# Fri3d_2024_Exp0_Keyboard_01.net
KiCad netlist of a schematic drawn in Altium Designer
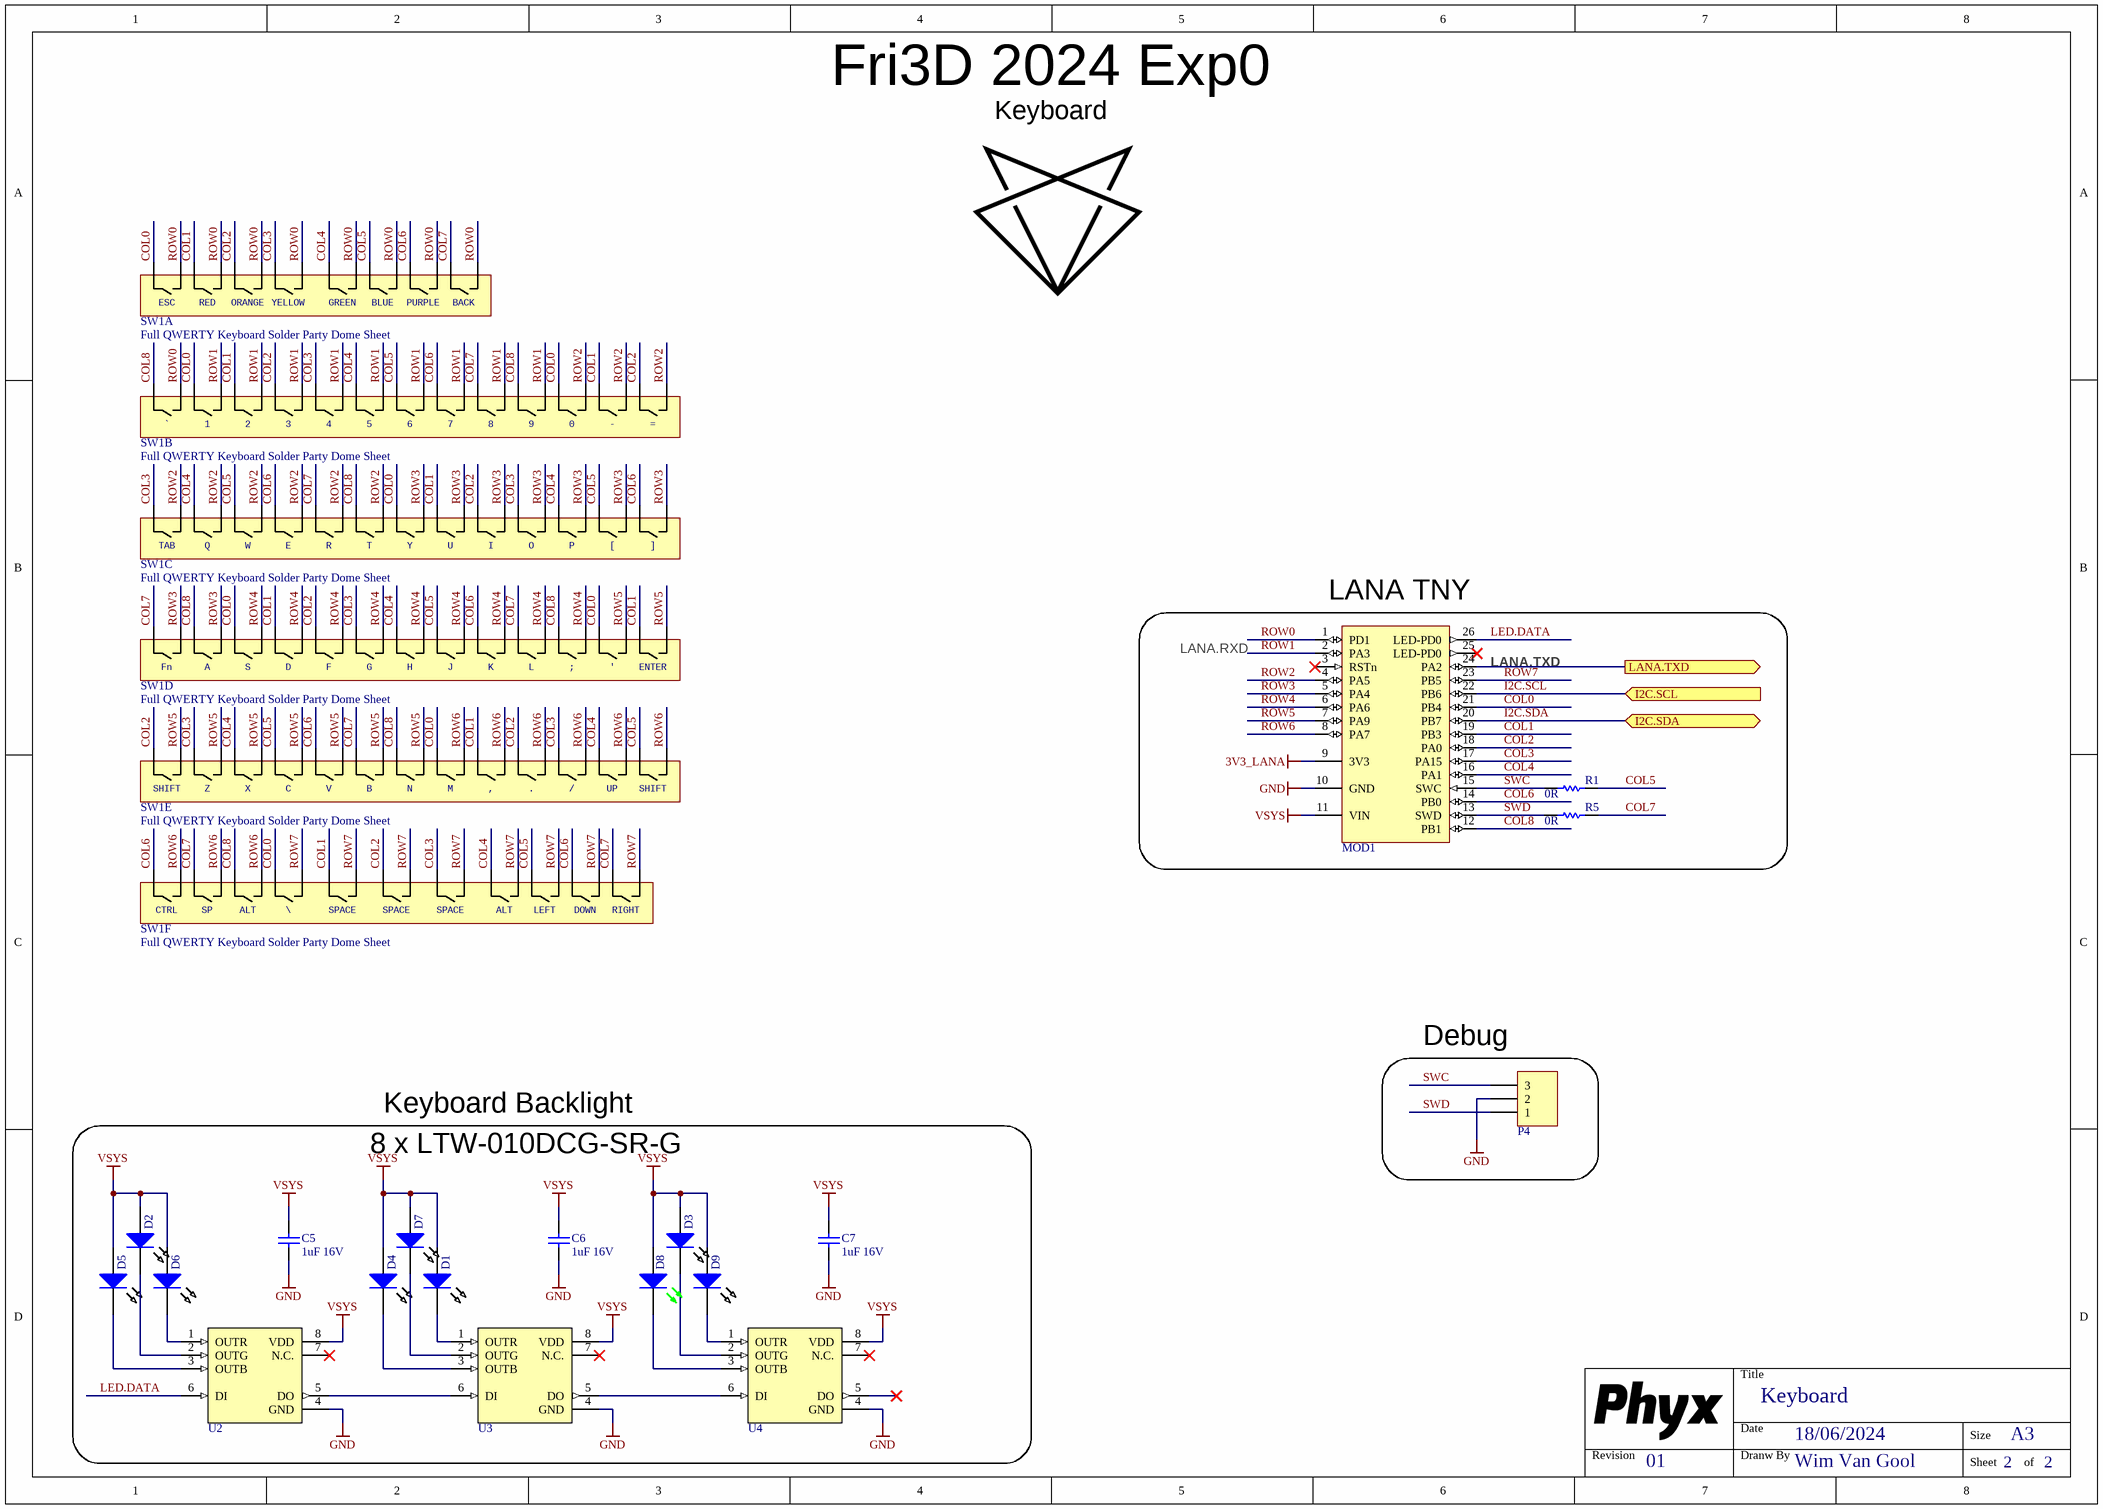
[diagram p0: Fri3d_2024_Exp0_Keyboard_01.SchDoc]

(export (version "E")
  (design (tool "Eeschema 10.0.6"))
  (components
    (comp (ref "C5")
      (value "1uF 16V")
      (footprint "C0603_N")
      (description "Capacitor Ceramic")
      (fields (field (name "Comment") "CAP_CERAMIC"))
      (libsource (lib "Phyx_Components") (part "CAP_CERAMIC"))
    )
    (comp (ref "C6")
      (value "1uF 16V")
      (footprint "C0603_N")
      (description "Capacitor Ceramic")
      (fields (field (name "Comment") "CAP_CERAMIC"))
      (libsource (lib "Phyx_Components") (part "CAP_CERAMIC"))
    )
    (comp (ref "C7")
      (value "1uF 16V")
      (footprint "C0603_N")
      (description "Capacitor Ceramic")
      (fields (field (name "Comment") "CAP_CERAMIC"))
      (libsource (lib "Phyx_Components") (part "CAP_CERAMIC"))
    )
    (comp (ref "D1")
      (value "Side emitting Cool White LED 3.0V 30mA 120° 2900mcd")
      (footprint "LITE_LTW-010DCG")
      (description "=Description")
      (libsource (lib "Phyx_Components") (part "LED_WHITE"))
    )
    (comp (ref "D2")
      (value "Side emitting Cool White LED 3.0V 30mA 120° 2900mcd")
      (footprint "LITE_LTW-010DCG")
      (description "=Description")
      (libsource (lib "Phyx_Components") (part "LED_WHITE"))
    )
    (comp (ref "D3")
      (value "Side emitting Cool White LED 3.0V 30mA 120° 2900mcd")
      (footprint "LITE_LTW-010DCG")
      (description "=Description")
      (libsource (lib "Phyx_Components") (part "LED_WHITE"))
    )
    (comp (ref "D4")
      (value "Side emitting Cool White LED 3.0V 30mA 120° 2900mcd")
      (footprint "LITE_LTW-010DCG")
      (description "=Description")
      (libsource (lib "Phyx_Components") (part "LED_WHITE"))
    )
    (comp (ref "D5")
      (value "Side emitting Cool White LED 3.0V 30mA 120° 2900mcd")
      (footprint "LITE_LTW-010DCG")
      (description "=Description")
      (libsource (lib "Phyx_Components") (part "LED_WHITE"))
    )
    (comp (ref "D6")
      (value "Side emitting Cool White LED 3.0V 30mA 120° 2900mcd")
      (footprint "LITE_LTW-010DCG")
      (description "=Description")
      (libsource (lib "Phyx_Components") (part "LED_WHITE"))
    )
    (comp (ref "D7")
      (value "Side emitting Cool White LED 3.0V 30mA 120° 2900mcd")
      (footprint "LITE_LTW-010DCG")
      (description "=Description")
      (libsource (lib "Phyx_Components") (part "LED_WHITE"))
    )
    (comp (ref "D8")
      (value "Default 0805 Green LED")
      (footprint "LED_0805_GR")
      (description "=Description")
      (libsource (lib "Phyx_Components") (part "LED_GREEN"))
    )
    (comp (ref "D9")
      (value "Side emitting Cool White LED 3.0V 30mA 120° 2900mcd")
      (footprint "LITE_LTW-010DCG")
      (description "=Description")
      (libsource (lib "Phyx_Components") (part "LED_WHITE"))
    )
    (comp (ref "MOD1")
      (value "CH23V203 based TNY module")
      (footprint "PHYX_LANA_TNY_SMD")
      (libsource (lib "Phyx_Components") (part "PHYX_LANA_TNY_SMD"))
    )
    (comp (ref "P4")
      (value "Header 3")
      (footprint "HDR1X3")
      (libsource (lib "Phyx_Components") (part "Header 3"))
    )
    (comp (ref "R1")
      (value "0R")
      (footprint "R0603_N")
      (fields (field (name "Comment") "RESISTOR"))
      (libsource (lib "Phyx_Components") (part "RESISTOR"))
    )
    (comp (ref "R5")
      (value "0R")
      (footprint "R0603_N")
      (fields (field (name "Comment") "RESISTOR"))
      (libsource (lib "Phyx_Components") (part "RESISTOR"))
    )
    (comp (ref "SW1")
      (value "Full QWERTY Keyboard Solder Party Dome Sheet")
      (footprint "Solder_Party_Keyb")
      (libsource (lib "CONNECTORS") (part "Solder_Party_Keyb"))
    )
    (comp (ref "U2")
      (value "3 Channel CC LED Driver 20mA")
      (footprint "WS_FSOP-8")
      (description "WS2811F 3-Ch LED Driver")
      (libsource (lib "Phyx_Components") (part "WS_WS2811F"))
    )
    (comp (ref "U3")
      (value "3 Channel CC LED Driver 20mA")
      (footprint "WS_FSOP-8")
      (description "WS2811F 3-Ch LED Driver")
      (libsource (lib "Phyx_Components") (part "WS_WS2811F"))
    )
    (comp (ref "U4")
      (value "3 Channel CC LED Driver 20mA")
      (footprint "WS_FSOP-8")
      (description "WS2811F 3-Ch LED Driver")
      (libsource (lib "Phyx_Components") (part "WS_WS2811F"))
    )
  )
  (nets
    (net (code "2") (name "/COL0") (class "Default")
      (node (ref "MOD1") (pin "21") (pinfunction "PB4_21") (pintype "bidirectional"))
      (node (ref "SW1") (pin "1") (pinfunction "1_1") (pintype "passive"))
      (node (ref "SW1") (pin "109") (pinfunction "109_109") (pintype "passive"))
      (node (ref "SW1") (pin "127") (pinfunction "127_127") (pintype "passive"))
      (node (ref "SW1") (pin "19") (pinfunction "19_19") (pintype "passive"))
      (node (ref "SW1") (pin "37") (pinfunction "37_37") (pintype "passive"))
      (node (ref "SW1") (pin "55") (pinfunction "55_55") (pintype "passive"))
      (node (ref "SW1") (pin "73") (pinfunction "73_73") (pintype "passive"))
      (node (ref "SW1") (pin "91") (pinfunction "91_91") (pintype "passive"))
    )
    (net (code "3") (name "/COL1") (class "Default")
      (node (ref "MOD1") (pin "19") (pinfunction "PB3_19") (pintype "bidirectional"))
      (node (ref "SW1") (pin "111") (pinfunction "111_111") (pintype "passive"))
      (node (ref "SW1") (pin "129") (pinfunction "129_129") (pintype "passive"))
      (node (ref "SW1") (pin "21") (pinfunction "21_21") (pintype "passive"))
      (node (ref "SW1") (pin "3") (pinfunction "3_3") (pintype "passive"))
      (node (ref "SW1") (pin "39") (pinfunction "39_39") (pintype "passive"))
      (node (ref "SW1") (pin "57") (pinfunction "57_57") (pintype "passive"))
      (node (ref "SW1") (pin "75") (pinfunction "75_75") (pintype "passive"))
      (node (ref "SW1") (pin "93") (pinfunction "93_93") (pintype "passive"))
    )
    (net (code "4") (name "/COL2") (class "Default")
      (node (ref "MOD1") (pin "18") (pinfunction "PA0_18") (pintype "bidirectional"))
      (node (ref "SW1") (pin "113") (pinfunction "113_113") (pintype "passive"))
      (node (ref "SW1") (pin "131") (pinfunction "131_131") (pintype "passive"))
      (node (ref "SW1") (pin "23") (pinfunction "23_23") (pintype "passive"))
      (node (ref "SW1") (pin "41") (pinfunction "41_41") (pintype "passive"))
      (node (ref "SW1") (pin "5") (pinfunction "5_5") (pintype "passive"))
      (node (ref "SW1") (pin "59") (pinfunction "59_59") (pintype "passive"))
      (node (ref "SW1") (pin "77") (pinfunction "77_77") (pintype "passive"))
      (node (ref "SW1") (pin "95") (pinfunction "95_95") (pintype "passive"))
    )
    (net (code "5") (name "/COL3") (class "Default")
      (node (ref "MOD1") (pin "17") (pinfunction "PA15_17") (pintype "bidirectional"))
      (node (ref "SW1") (pin "115") (pinfunction "115_115") (pintype "passive"))
      (node (ref "SW1") (pin "133") (pinfunction "133_133") (pintype "passive"))
      (node (ref "SW1") (pin "25") (pinfunction "25_25") (pintype "passive"))
      (node (ref "SW1") (pin "43") (pinfunction "43_43") (pintype "passive"))
      (node (ref "SW1") (pin "61") (pinfunction "61_61") (pintype "passive"))
      (node (ref "SW1") (pin "7") (pinfunction "7_7") (pintype "passive"))
      (node (ref "SW1") (pin "79") (pinfunction "79_79") (pintype "passive"))
      (node (ref "SW1") (pin "97") (pinfunction "97_97") (pintype "passive"))
    )
    (net (code "6") (name "/COL4") (class "Default")
      (node (ref "MOD1") (pin "16") (pinfunction "PA1_16") (pintype "bidirectional"))
      (node (ref "SW1") (pin "117") (pinfunction "117_117") (pintype "passive"))
      (node (ref "SW1") (pin "135") (pinfunction "135_135") (pintype "passive"))
      (node (ref "SW1") (pin "27") (pinfunction "27_27") (pintype "passive"))
      (node (ref "SW1") (pin "45") (pinfunction "45_45") (pintype "passive"))
      (node (ref "SW1") (pin "63") (pinfunction "63_63") (pintype "passive"))
      (node (ref "SW1") (pin "81") (pinfunction "81_81") (pintype "passive"))
      (node (ref "SW1") (pin "9") (pinfunction "9_9") (pintype "passive"))
      (node (ref "SW1") (pin "99") (pinfunction "99_99") (pintype "passive"))
    )
    (net (code "7") (name "/COL5") (class "Default")
      (node (ref "R1") (pin "1") (pinfunction "1_1") (pintype "passive"))
      (node (ref "SW1") (pin "101") (pinfunction "101_101") (pintype "passive"))
      (node (ref "SW1") (pin "11") (pinfunction "11_11") (pintype "passive"))
      (node (ref "SW1") (pin "119") (pinfunction "119_119") (pintype "passive"))
      (node (ref "SW1") (pin "137") (pinfunction "137_137") (pintype "passive"))
      (node (ref "SW1") (pin "29") (pinfunction "29_29") (pintype "passive"))
      (node (ref "SW1") (pin "47") (pinfunction "47_47") (pintype "passive"))
      (node (ref "SW1") (pin "65") (pinfunction "65_65") (pintype "passive"))
      (node (ref "SW1") (pin "83") (pinfunction "83_83") (pintype "passive"))
    )
    (net (code "8") (name "/COL6") (class "Default")
      (node (ref "MOD1") (pin "14") (pinfunction "PB0_14") (pintype "bidirectional"))
      (node (ref "SW1") (pin "103") (pinfunction "103_103") (pintype "passive"))
      (node (ref "SW1") (pin "121") (pinfunction "121_121") (pintype "passive"))
      (node (ref "SW1") (pin "13") (pinfunction "13_13") (pintype "passive"))
      (node (ref "SW1") (pin "139") (pinfunction "139_139") (pintype "passive"))
      (node (ref "SW1") (pin "31") (pinfunction "31_31") (pintype "passive"))
      (node (ref "SW1") (pin "49") (pinfunction "49_49") (pintype "passive"))
      (node (ref "SW1") (pin "67") (pinfunction "67_67") (pintype "passive"))
      (node (ref "SW1") (pin "85") (pinfunction "85_85") (pintype "passive"))
    )
    (net (code "9") (name "/COL7") (class "Default")
      (node (ref "R5") (pin "1") (pinfunction "1_1") (pintype "passive"))
      (node (ref "SW1") (pin "105") (pinfunction "105_105") (pintype "passive"))
      (node (ref "SW1") (pin "123") (pinfunction "123_123") (pintype "passive"))
      (node (ref "SW1") (pin "141") (pinfunction "141_141") (pintype "passive"))
      (node (ref "SW1") (pin "15") (pinfunction "15_15") (pintype "passive"))
      (node (ref "SW1") (pin "33") (pinfunction "33_33") (pintype "passive"))
      (node (ref "SW1") (pin "51") (pinfunction "51_51") (pintype "passive"))
      (node (ref "SW1") (pin "69") (pinfunction "69_69") (pintype "passive"))
      (node (ref "SW1") (pin "87") (pinfunction "87_87") (pintype "passive"))
    )
    (net (code "10") (name "/COL8") (class "Default")
      (node (ref "MOD1") (pin "12") (pinfunction "PB1_12") (pintype "bidirectional"))
      (node (ref "SW1") (pin "107") (pinfunction "107_107") (pintype "passive"))
      (node (ref "SW1") (pin "125") (pinfunction "125_125") (pintype "passive"))
      (node (ref "SW1") (pin "17") (pinfunction "17_17") (pintype "passive"))
      (node (ref "SW1") (pin "35") (pinfunction "35_35") (pintype "passive"))
      (node (ref "SW1") (pin "53") (pinfunction "53_53") (pintype "passive"))
      (node (ref "SW1") (pin "71") (pinfunction "71_71") (pintype "passive"))
      (node (ref "SW1") (pin "89") (pinfunction "89_89") (pintype "passive"))
    )
    (net (code "11") (name "/I2C.SCL") (class "Default")
      (node (ref "MOD1") (pin "22") (pinfunction "PB6_22") (pintype "bidirectional"))
    )
    (net (code "12") (name "/I2C.SDA") (class "Default")
      (node (ref "MOD1") (pin "20") (pinfunction "PB7_20") (pintype "bidirectional"))
    )
    (net (code "13") (name "/LANA.TXD") (class "Default")
      (node (ref "MOD1") (pin "24") (pinfunction "PA2_24") (pintype "bidirectional"))
    )
    (net (code "14") (name "/LED.DATA") (class "Default")
      (node (ref "MOD1") (pin "26") (pinfunction "LED-PD0_26") (pintype "output"))
      (node (ref "U2") (pin "6") (pinfunction "DI_6") (pintype "input"))
    )
    (net (code "15") (name "/ROW0") (class "Default")
      (node (ref "MOD1") (pin "1") (pinfunction "PD1_1") (pintype "bidirectional"))
      (node (ref "SW1") (pin "10") (pinfunction "10_10") (pintype "passive"))
      (node (ref "SW1") (pin "12") (pinfunction "12_12") (pintype "passive"))
      (node (ref "SW1") (pin "14") (pinfunction "14_14") (pintype "passive"))
      (node (ref "SW1") (pin "16") (pinfunction "16_16") (pintype "passive"))
      (node (ref "SW1") (pin "18") (pinfunction "18_18") (pintype "passive"))
      (node (ref "SW1") (pin "2") (pinfunction "2_2") (pintype "passive"))
      (node (ref "SW1") (pin "4") (pinfunction "4_4") (pintype "passive"))
      (node (ref "SW1") (pin "6") (pinfunction "6_6") (pintype "passive"))
      (node (ref "SW1") (pin "8") (pinfunction "8_8") (pintype "passive"))
    )
    (net (code "16") (name "/ROW1") (class "Default")
      (node (ref "MOD1") (pin "2") (pinfunction "PA3_2") (pintype "bidirectional"))
      (node (ref "SW1") (pin "20") (pinfunction "20_20") (pintype "passive"))
      (node (ref "SW1") (pin "22") (pinfunction "22_22") (pintype "passive"))
      (node (ref "SW1") (pin "24") (pinfunction "24_24") (pintype "passive"))
      (node (ref "SW1") (pin "26") (pinfunction "26_26") (pintype "passive"))
      (node (ref "SW1") (pin "28") (pinfunction "28_28") (pintype "passive"))
      (node (ref "SW1") (pin "30") (pinfunction "30_30") (pintype "passive"))
      (node (ref "SW1") (pin "32") (pinfunction "32_32") (pintype "passive"))
      (node (ref "SW1") (pin "34") (pinfunction "34_34") (pintype "passive"))
      (node (ref "SW1") (pin "36") (pinfunction "36_36") (pintype "passive"))
    )
    (net (code "17") (name "/ROW2") (class "Default")
      (node (ref "MOD1") (pin "4") (pinfunction "PA5_4") (pintype "bidirectional"))
      (node (ref "SW1") (pin "38") (pinfunction "38_38") (pintype "passive"))
      (node (ref "SW1") (pin "40") (pinfunction "40_40") (pintype "passive"))
      (node (ref "SW1") (pin "42") (pinfunction "42_42") (pintype "passive"))
      (node (ref "SW1") (pin "44") (pinfunction "44_44") (pintype "passive"))
      (node (ref "SW1") (pin "46") (pinfunction "46_46") (pintype "passive"))
      (node (ref "SW1") (pin "48") (pinfunction "48_48") (pintype "passive"))
      (node (ref "SW1") (pin "50") (pinfunction "50_50") (pintype "passive"))
      (node (ref "SW1") (pin "52") (pinfunction "52_52") (pintype "passive"))
      (node (ref "SW1") (pin "54") (pinfunction "54_54") (pintype "passive"))
    )
    (net (code "18") (name "/ROW3") (class "Default")
      (node (ref "MOD1") (pin "5") (pinfunction "PA4_5") (pintype "bidirectional"))
      (node (ref "SW1") (pin "56") (pinfunction "56_56") (pintype "passive"))
      (node (ref "SW1") (pin "58") (pinfunction "58_58") (pintype "passive"))
      (node (ref "SW1") (pin "60") (pinfunction "60_60") (pintype "passive"))
      (node (ref "SW1") (pin "62") (pinfunction "62_62") (pintype "passive"))
      (node (ref "SW1") (pin "64") (pinfunction "64_64") (pintype "passive"))
      (node (ref "SW1") (pin "66") (pinfunction "66_66") (pintype "passive"))
      (node (ref "SW1") (pin "68") (pinfunction "68_68") (pintype "passive"))
      (node (ref "SW1") (pin "70") (pinfunction "70_70") (pintype "passive"))
      (node (ref "SW1") (pin "72") (pinfunction "72_72") (pintype "passive"))
    )
    (net (code "19") (name "/ROW4") (class "Default")
      (node (ref "MOD1") (pin "6") (pinfunction "PA6_6") (pintype "bidirectional"))
      (node (ref "SW1") (pin "74") (pinfunction "74_74") (pintype "passive"))
      (node (ref "SW1") (pin "76") (pinfunction "76_76") (pintype "passive"))
      (node (ref "SW1") (pin "78") (pinfunction "78_78") (pintype "passive"))
      (node (ref "SW1") (pin "80") (pinfunction "80_80") (pintype "passive"))
      (node (ref "SW1") (pin "82") (pinfunction "82_82") (pintype "passive"))
      (node (ref "SW1") (pin "84") (pinfunction "84_84") (pintype "passive"))
      (node (ref "SW1") (pin "86") (pinfunction "86_86") (pintype "passive"))
      (node (ref "SW1") (pin "88") (pinfunction "88_88") (pintype "passive"))
      (node (ref "SW1") (pin "90") (pinfunction "90_90") (pintype "passive"))
    )
    (net (code "20") (name "/ROW5") (class "Default")
      (node (ref "MOD1") (pin "7") (pinfunction "PA9_7") (pintype "bidirectional"))
      (node (ref "SW1") (pin "100") (pinfunction "100_100") (pintype "passive"))
      (node (ref "SW1") (pin "102") (pinfunction "102_102") (pintype "passive"))
      (node (ref "SW1") (pin "104") (pinfunction "104_104") (pintype "passive"))
      (node (ref "SW1") (pin "106") (pinfunction "106_106") (pintype "passive"))
      (node (ref "SW1") (pin "108") (pinfunction "108_108") (pintype "passive"))
      (node (ref "SW1") (pin "92") (pinfunction "92_92") (pintype "passive"))
      (node (ref "SW1") (pin "94") (pinfunction "94_94") (pintype "passive"))
      (node (ref "SW1") (pin "96") (pinfunction "96_96") (pintype "passive"))
      (node (ref "SW1") (pin "98") (pinfunction "98_98") (pintype "passive"))
    )
    (net (code "21") (name "/ROW6") (class "Default")
      (node (ref "MOD1") (pin "8") (pinfunction "PA7_8") (pintype "bidirectional"))
      (node (ref "SW1") (pin "110") (pinfunction "110_110") (pintype "passive"))
      (node (ref "SW1") (pin "112") (pinfunction "112_112") (pintype "passive"))
      (node (ref "SW1") (pin "114") (pinfunction "114_114") (pintype "passive"))
      (node (ref "SW1") (pin "116") (pinfunction "116_116") (pintype "passive"))
      (node (ref "SW1") (pin "118") (pinfunction "118_118") (pintype "passive"))
      (node (ref "SW1") (pin "120") (pinfunction "120_120") (pintype "passive"))
      (node (ref "SW1") (pin "122") (pinfunction "122_122") (pintype "passive"))
      (node (ref "SW1") (pin "124") (pinfunction "124_124") (pintype "passive"))
      (node (ref "SW1") (pin "126") (pinfunction "126_126") (pintype "passive"))
    )
    (net (code "22") (name "/ROW7") (class "Default")
      (node (ref "MOD1") (pin "23") (pinfunction "PB5_23") (pintype "bidirectional"))
      (node (ref "SW1") (pin "128") (pinfunction "128_128") (pintype "passive"))
      (node (ref "SW1") (pin "130") (pinfunction "130_130") (pintype "passive"))
      (node (ref "SW1") (pin "132") (pinfunction "132_132") (pintype "passive"))
      (node (ref "SW1") (pin "134") (pinfunction "134_134") (pintype "passive"))
      (node (ref "SW1") (pin "136") (pinfunction "136_136") (pintype "passive"))
      (node (ref "SW1") (pin "138") (pinfunction "138_138") (pintype "passive"))
      (node (ref "SW1") (pin "140") (pinfunction "140_140") (pintype "passive"))
      (node (ref "SW1") (pin "142") (pinfunction "142_142") (pintype "passive"))
    )
    (net (code "23") (name "/SWC") (class "Default")
      (node (ref "MOD1") (pin "15") (pinfunction "SWC_15") (pintype "input"))
      (node (ref "P4") (pin "3") (pinfunction "3_3") (pintype "passive"))
      (node (ref "R1") (pin "2") (pinfunction "2_2") (pintype "passive"))
    )
    (net (code "24") (name "/SWD") (class "Default")
      (node (ref "MOD1") (pin "13") (pinfunction "SWD_13") (pintype "bidirectional"))
      (node (ref "P4") (pin "1") (pinfunction "1_1") (pintype "passive"))
      (node (ref "R5") (pin "2") (pinfunction "2_2") (pintype "passive"))
    )
    (net (code "25") (name "3V3_LANA") (class "Default")
      (node (ref "MOD1") (pin "9") (pinfunction "3V3_9") (pintype "power_in"))
    )
    (net (code "26") (name "GND") (class "Default")
      (node (ref "C5") (pin "2") (pinfunction "2_2") (pintype "passive"))
      (node (ref "C6") (pin "2") (pinfunction "2_2") (pintype "passive"))
      (node (ref "C7") (pin "2") (pinfunction "2_2") (pintype "passive"))
      (node (ref "MOD1") (pin "10") (pinfunction "GND_10") (pintype "power_in"))
      (node (ref "P4") (pin "2") (pinfunction "2_2") (pintype "passive"))
      (node (ref "U2") (pin "4") (pinfunction "GND_4") (pintype "power_in"))
      (node (ref "U3") (pin "4") (pinfunction "GND_4") (pintype "power_in"))
      (node (ref "U4") (pin "4") (pinfunction "GND_4") (pintype "power_in"))
    )
    (net (code "27") (name "Net-(D1-K)") (class "Default")
      (node (ref "D1") (pin "2") (pinfunction "K_2") (pintype "passive"))
      (node (ref "U3") (pin "1") (pinfunction "OUTR_1") (pintype "input"))
    )
    (net (code "28") (name "Net-(D2-K)") (class "Default")
      (node (ref "D2") (pin "2") (pinfunction "K_2") (pintype "passive"))
      (node (ref "U2") (pin "2") (pinfunction "OUTG_2") (pintype "input"))
    )
    (net (code "29") (name "Net-(D3-K)") (class "Default")
      (node (ref "D3") (pin "2") (pinfunction "K_2") (pintype "passive"))
      (node (ref "U4") (pin "2") (pinfunction "OUTG_2") (pintype "input"))
    )
    (net (code "30") (name "Net-(D4-K)") (class "Default")
      (node (ref "D4") (pin "2") (pinfunction "K_2") (pintype "passive"))
      (node (ref "U3") (pin "3") (pinfunction "OUTB_3") (pintype "input"))
    )
    (net (code "31") (name "Net-(D5-K)") (class "Default")
      (node (ref "D5") (pin "2") (pinfunction "K_2") (pintype "passive"))
      (node (ref "U2") (pin "3") (pinfunction "OUTB_3") (pintype "input"))
    )
    (net (code "32") (name "Net-(D6-K)") (class "Default")
      (node (ref "D6") (pin "2") (pinfunction "K_2") (pintype "passive"))
      (node (ref "U2") (pin "1") (pinfunction "OUTR_1") (pintype "input"))
    )
    (net (code "33") (name "Net-(D7-K)") (class "Default")
      (node (ref "D7") (pin "2") (pinfunction "K_2") (pintype "passive"))
      (node (ref "U3") (pin "2") (pinfunction "OUTG_2") (pintype "input"))
    )
    (net (code "34") (name "Net-(D8-K)") (class "Default")
      (node (ref "D8") (pin "2") (pinfunction "K_2") (pintype "passive"))
      (node (ref "U4") (pin "3") (pinfunction "OUTB_3") (pintype "input"))
    )
    (net (code "35") (name "Net-(D9-K)") (class "Default")
      (node (ref "D9") (pin "2") (pinfunction "K_2") (pintype "passive"))
      (node (ref "U4") (pin "1") (pinfunction "OUTR_1") (pintype "input"))
    )
    (net (code "36") (name "Net-(U2-DO)") (class "Default")
      (node (ref "U2") (pin "5") (pinfunction "DO_5") (pintype "output"))
      (node (ref "U3") (pin "6") (pinfunction "DI_6") (pintype "input"))
    )
    (net (code "37") (name "Net-(U3-DO)") (class "Default")
      (node (ref "U3") (pin "5") (pinfunction "DO_5") (pintype "output"))
      (node (ref "U4") (pin "6") (pinfunction "DI_6") (pintype "input"))
    )
    (net (code "38") (name "VSYS") (class "Default")
      (node (ref "C5") (pin "1") (pinfunction "1_1") (pintype "passive"))
      (node (ref "C6") (pin "1") (pinfunction "1_1") (pintype "passive"))
      (node (ref "C7") (pin "1") (pinfunction "1_1") (pintype "passive"))
      (node (ref "D1") (pin "1") (pinfunction "A_1") (pintype "passive"))
      (node (ref "D2") (pin "1") (pinfunction "A_1") (pintype "passive"))
      (node (ref "D3") (pin "1") (pinfunction "A_1") (pintype "passive"))
      (node (ref "D4") (pin "1") (pinfunction "A_1") (pintype "passive"))
      (node (ref "D5") (pin "1") (pinfunction "A_1") (pintype "passive"))
      (node (ref "D6") (pin "1") (pinfunction "A_1") (pintype "passive"))
      (node (ref "D7") (pin "1") (pinfunction "A_1") (pintype "passive"))
      (node (ref "D8") (pin "1") (pinfunction "A_1") (pintype "passive"))
      (node (ref "D9") (pin "1") (pinfunction "A_1") (pintype "passive"))
      (node (ref "MOD1") (pin "11") (pinfunction "VIN_11") (pintype "power_in"))
      (node (ref "U2") (pin "8") (pinfunction "VDD_8") (pintype "power_in"))
      (node (ref "U3") (pin "8") (pinfunction "VDD_8") (pintype "power_in"))
      (node (ref "U4") (pin "8") (pinfunction "VDD_8") (pintype "power_in"))
    )
    (net (code "39") (name "unconnected-(MOD1-LED-PD0-Pad25)") (class "Default")
      (node (ref "MOD1") (pin "25") (pinfunction "LED-PD0_25") (pintype "output+no_connect"))
    )
    (net (code "40") (name "unconnected-(MOD1-RSTn-Pad3)") (class "Default")
      (node (ref "MOD1") (pin "3") (pinfunction "RSTn_3") (pintype "input+no_connect"))
    )
    (net (code "41") (name "unconnected-(U2-N.C.-Pad7)") (class "Default")
      (node (ref "U2") (pin "7") (pinfunction "N.C._7") (pintype "passive+no_connect"))
    )
    (net (code "42") (name "unconnected-(U3-N.C.-Pad7)") (class "Default")
      (node (ref "U3") (pin "7") (pinfunction "N.C._7") (pintype "passive+no_connect"))
    )
    (net (code "43") (name "unconnected-(U4-DO-Pad5)") (class "Default")
      (node (ref "U4") (pin "5") (pinfunction "DO_5") (pintype "output+no_connect"))
    )
    (net (code "44") (name "unconnected-(U4-N.C.-Pad7)") (class "Default")
      (node (ref "U4") (pin "7") (pinfunction "N.C._7") (pintype "passive+no_connect"))
    )
  )
)
